# USB-C_BREAKOUT_COMPONENTS.net
KiCad netlist of a schematic drawn in Altium Designer
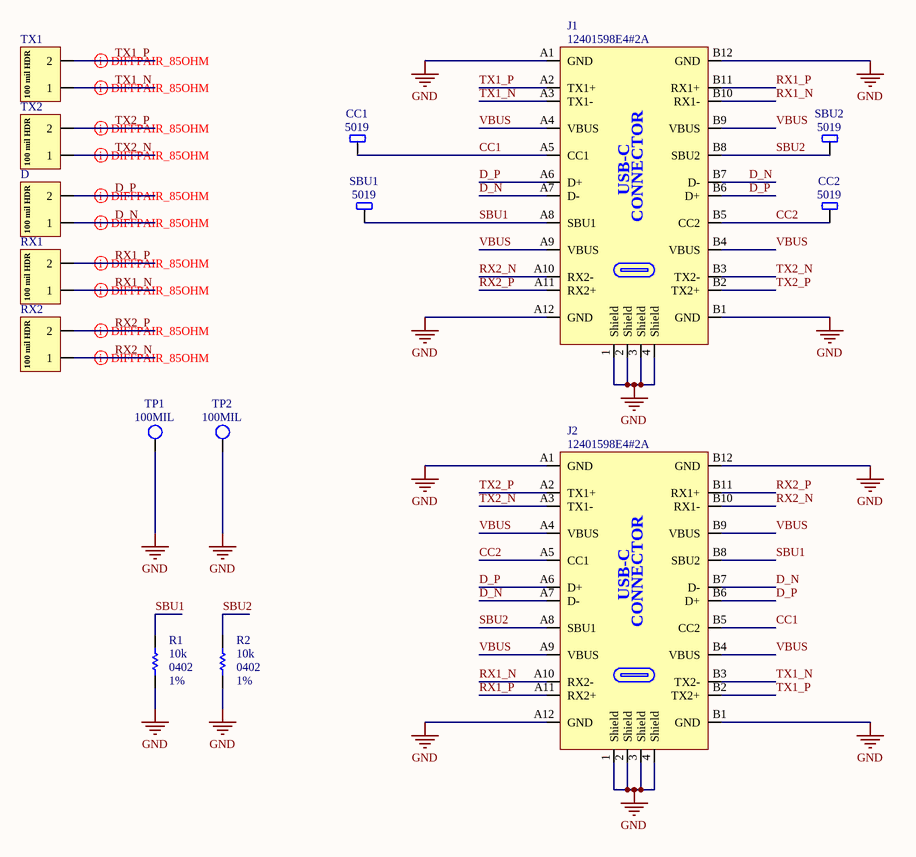
[diagram p0: USB-C_BREAKOUT_COMPONENTS.SchDoc]

(export (version "E")
  (design (tool "Eeschema 10.0.6"))
  (components
    (comp (ref "CC1")
      (value "5019")
      (footprint "GRAMS_MASTER_LIB_PCB:TPO_SMD_5019")
      (description "TPO - PC TEST POINT MINI - SMD")
      (fields
        (field (name "CREATEDBY/DATE") "Olivier Bernard / 5/12/2017")
        (field (name "VERIFIEDBY") "Caroline Paulin / 5 juillet 2018")
      )
      (libsource (lib "GRAMS_MASTER_LIB_SCH") (part "TPO_SMD_5019"))
    )
    (comp (ref "CC2")
      (value "5019")
      (footprint "GRAMS_MASTER_LIB_PCB:TPO_SMD_5019")
      (description "TPO - PC TEST POINT MINI - SMD")
      (fields
        (field (name "CREATEDBY/DATE") "Olivier Bernard / 5/12/2017")
        (field (name "VERIFIEDBY") "Caroline Paulin / 5 juillet 2018")
      )
      (libsource (lib "GRAMS_MASTER_LIB_SCH") (part "TPO_SMD_5019"))
    )
    (comp (ref "D")
      (value "TS-102-G-A")
      (footprint "GRAMS_MASTER_LIB_PCB:CON_HDR_TS-102-G-A")
      (description "CON - HDR 2 position 0.100\" - TH")
      (fields
        (field (name "CREATEDBY/DATE") "Joel Lemay 2018-06-19")
        (field (name "VERIFIEDBY") "Caroline Paulin - 10 sept 2018")
      )
      (libsource (lib "GRAMS_MASTER_LIB_SCH") (part "CON_HDR_TS-102-G-A"))
    )
    (comp (ref "J1")
      (value "12401598E4#2A")
      (footprint "CON_USB_3.2_TypeC_12401598E4#2A")
      (description "CON_USB - USB 3.2 Gen 2 (USB 3.1 Gen 2, Superspeed + (USB 3.1)) 24 pos Receptacle - R/A")
      (fields
        (field (name "CREATEDBY/DATE") "Louis-Daniel Gaulin / 07-04-2021")
        (field (name "VERIFIEDBY") "Philippe Arsenault/2021-04-08")
      )
      (libsource (lib "SWARMUS_LIB") (part "CON_USB_3.2_TypeC_12401598E4#2A"))
    )
    (comp (ref "J2")
      (value "12401598E4#2A")
      (footprint "CON_USB_3.2_TypeC_12401598E4#2A")
      (description "CON_USB - USB 3.2 Gen 2 (USB 3.1 Gen 2, Superspeed + (USB 3.1)) 24 pos Receptacle - R/A")
      (fields
        (field (name "CREATEDBY/DATE") "Louis-Daniel Gaulin / 07-04-2021")
        (field (name "VERIFIEDBY") "Philippe Arsenault/2021-04-08")
      )
      (libsource (lib "SWARMUS_LIB") (part "CON_USB_3.2_TypeC_12401598E4#2A"))
    )
    (comp (ref "R1")
      (value "10k")
      (footprint "GRAMS_MASTER_LIB_PCB:RES_0402")
      (description "RES - 10K OHMS 1% 1/16W - 0402")
      (fields
        (field (name "TOLERANCE") "1%")
        (field (name "PACKAGE") "0402")
        (field (name "Comment") "RC0402FR-0710KL")
        (field (name "CREATEDBY/DATE") "Nicolas V. (2018-11-20)")
        (field (name "VERIFIEDBY") "Nicolas V. (2018-11-20)")
      )
      (libsource (lib "GRAMS_MASTER_LIB_SCH") (part "RES_RC0402FR-0710KL"))
    )
    (comp (ref "R2")
      (value "10k")
      (footprint "GRAMS_MASTER_LIB_PCB:RES_0402")
      (description "RES - 10K OHMS 1% 1/16W - 0402")
      (fields
        (field (name "TOLERANCE") "1%")
        (field (name "PACKAGE") "0402")
        (field (name "Comment") "RC0402FR-0710KL")
        (field (name "CREATEDBY/DATE") "Nicolas V. (2018-11-20)")
        (field (name "VERIFIEDBY") "Nicolas V. (2018-11-20)")
      )
      (libsource (lib "GRAMS_MASTER_LIB_SCH") (part "RES_RC0402FR-0710KL"))
    )
    (comp (ref "RX1")
      (value "TS-102-G-A")
      (footprint "GRAMS_MASTER_LIB_PCB:CON_HDR_TS-102-G-A")
      (description "CON - HDR 2 position 0.100\" - TH")
      (fields
        (field (name "CREATEDBY/DATE") "Joel Lemay 2018-06-19")
        (field (name "VERIFIEDBY") "Caroline Paulin - 10 sept 2018")
      )
      (libsource (lib "GRAMS_MASTER_LIB_SCH") (part "CON_HDR_TS-102-G-A"))
    )
    (comp (ref "RX2")
      (value "TS-102-G-A")
      (footprint "GRAMS_MASTER_LIB_PCB:CON_HDR_TS-102-G-A")
      (description "CON - HDR 2 position 0.100\" - TH")
      (fields
        (field (name "CREATEDBY/DATE") "Joel Lemay 2018-06-19")
        (field (name "VERIFIEDBY") "Caroline Paulin - 10 sept 2018")
      )
      (libsource (lib "GRAMS_MASTER_LIB_SCH") (part "CON_HDR_TS-102-G-A"))
    )
    (comp (ref "SBU1")
      (value "5019")
      (footprint "GRAMS_MASTER_LIB_PCB:TPO_SMD_5019")
      (description "TPO - PC TEST POINT MINI - SMD")
      (fields
        (field (name "CREATEDBY/DATE") "Olivier Bernard / 5/12/2017")
        (field (name "VERIFIEDBY") "Caroline Paulin / 5 juillet 2018")
      )
      (libsource (lib "GRAMS_MASTER_LIB_SCH") (part "TPO_SMD_5019"))
    )
    (comp (ref "SBU2")
      (value "5019")
      (footprint "GRAMS_MASTER_LIB_PCB:TPO_SMD_5019")
      (description "TPO - PC TEST POINT MINI - SMD")
      (fields
        (field (name "CREATEDBY/DATE") "Olivier Bernard / 5/12/2017")
        (field (name "VERIFIEDBY") "Caroline Paulin / 5 juillet 2018")
      )
      (libsource (lib "GRAMS_MASTER_LIB_SCH") (part "TPO_SMD_5019"))
    )
    (comp (ref "TP1")
      (value "100MIL")
      (footprint "grams_master_lib_pcb:TPO_TH_ROUND_100MIL")
      (description "TPO - TEST POINT ROUND TH  - 100MIL")
      (fields
        (field (name "CREATEDBY/DATE") "Louis-Daniel Gaulin/ 14/01/2020")
        (field (name "VERIFIEDBY") "C.Paulin - 21/01/2020")
      )
      (libsource (lib "GRAMS_MASTER_LIB_SCH") (part "TPO_TH_ROUND_100MIL"))
    )
    (comp (ref "TP2")
      (value "100MIL")
      (footprint "grams_master_lib_pcb:TPO_TH_ROUND_100MIL")
      (description "TPO - TEST POINT ROUND TH  - 100MIL")
      (fields
        (field (name "CREATEDBY/DATE") "Louis-Daniel Gaulin/ 14/01/2020")
        (field (name "VERIFIEDBY") "C.Paulin - 21/01/2020")
      )
      (libsource (lib "GRAMS_MASTER_LIB_SCH") (part "TPO_TH_ROUND_100MIL"))
    )
    (comp (ref "TX1")
      (value "TS-102-G-A")
      (footprint "GRAMS_MASTER_LIB_PCB:CON_HDR_TS-102-G-A")
      (description "CON - HDR 2 position 0.100\" - TH")
      (fields
        (field (name "CREATEDBY/DATE") "Joel Lemay 2018-06-19")
        (field (name "VERIFIEDBY") "Caroline Paulin - 10 sept 2018")
      )
      (libsource (lib "GRAMS_MASTER_LIB_SCH") (part "CON_HDR_TS-102-G-A"))
    )
    (comp (ref "TX2")
      (value "TS-102-G-A")
      (footprint "GRAMS_MASTER_LIB_PCB:CON_HDR_TS-102-G-A")
      (description "CON - HDR 2 position 0.100\" - TH")
      (fields
        (field (name "CREATEDBY/DATE") "Joel Lemay 2018-06-19")
        (field (name "VERIFIEDBY") "Caroline Paulin - 10 sept 2018")
      )
      (libsource (lib "GRAMS_MASTER_LIB_SCH") (part "CON_HDR_TS-102-G-A"))
    )
  )
  (nets
    (net (code "1") (name "/CC1") (class "Default")
      (node (ref "CC1") (pin "1") (pinfunction "1_1") (pintype "passive"))
      (node (ref "J1") (pin "A5") (pinfunction "CC1_A5") (pintype "passive"))
      (node (ref "J2") (pin "B5") (pinfunction "CC2_B5") (pintype "passive"))
    )
    (net (code "2") (name "/CC2") (class "Default")
      (node (ref "CC2") (pin "1") (pinfunction "1_1") (pintype "passive"))
      (node (ref "J1") (pin "B5") (pinfunction "CC2_B5") (pintype "passive"))
      (node (ref "J2") (pin "A5") (pinfunction "CC1_A5") (pintype "passive"))
    )
    (net (code "3") (name "/D_N") (class "Default")
      (node (ref "D") (pin "1") (pinfunction "1_1") (pintype "passive"))
      (node (ref "J1") (pin "A7") (pinfunction "D-_A7") (pintype "passive"))
      (node (ref "J1") (pin "B7") (pinfunction "D-_B7") (pintype "passive"))
      (node (ref "J2") (pin "A7") (pinfunction "D-_A7") (pintype "passive"))
      (node (ref "J2") (pin "B7") (pinfunction "D-_B7") (pintype "passive"))
    )
    (net (code "4") (name "/D_P") (class "Default")
      (node (ref "D") (pin "2") (pinfunction "2_2") (pintype "passive"))
      (node (ref "J1") (pin "A6") (pinfunction "D+_A6") (pintype "passive"))
      (node (ref "J1") (pin "B6") (pinfunction "D+_B6") (pintype "passive"))
      (node (ref "J2") (pin "A6") (pinfunction "D+_A6") (pintype "passive"))
      (node (ref "J2") (pin "B6") (pinfunction "D+_B6") (pintype "passive"))
    )
    (net (code "5") (name "/RX1_N") (class "Default")
      (node (ref "J1") (pin "B10") (pinfunction "RX1-_B10") (pintype "passive"))
      (node (ref "J2") (pin "A10") (pinfunction "RX2-_A10") (pintype "passive"))
      (node (ref "RX1") (pin "1") (pinfunction "1_1") (pintype "passive"))
    )
    (net (code "6") (name "/RX1_P") (class "Default")
      (node (ref "J1") (pin "B11") (pinfunction "RX1+_B11") (pintype "passive"))
      (node (ref "J2") (pin "A11") (pinfunction "RX2+_A11") (pintype "passive"))
      (node (ref "RX1") (pin "2") (pinfunction "2_2") (pintype "passive"))
    )
    (net (code "7") (name "/RX2_N") (class "Default")
      (node (ref "J1") (pin "A10") (pinfunction "RX2-_A10") (pintype "passive"))
      (node (ref "J2") (pin "B10") (pinfunction "RX1-_B10") (pintype "passive"))
      (node (ref "RX2") (pin "1") (pinfunction "1_1") (pintype "passive"))
    )
    (net (code "8") (name "/RX2_P") (class "Default")
      (node (ref "J1") (pin "A11") (pinfunction "RX2+_A11") (pintype "passive"))
      (node (ref "J2") (pin "B11") (pinfunction "RX1+_B11") (pintype "passive"))
      (node (ref "RX2") (pin "2") (pinfunction "2_2") (pintype "passive"))
    )
    (net (code "9") (name "/SBU1") (class "Default")
      (node (ref "J1") (pin "A8") (pinfunction "SBU1_A8") (pintype "passive"))
      (node (ref "J2") (pin "B8") (pinfunction "SBU2_B8") (pintype "passive"))
      (node (ref "R1") (pin "1") (pinfunction "1_1") (pintype "passive"))
      (node (ref "SBU1") (pin "1") (pinfunction "1_1") (pintype "passive"))
    )
    (net (code "10") (name "/SBU2") (class "Default")
      (node (ref "J1") (pin "B8") (pinfunction "SBU2_B8") (pintype "passive"))
      (node (ref "J2") (pin "A8") (pinfunction "SBU1_A8") (pintype "passive"))
      (node (ref "R2") (pin "1") (pinfunction "1_1") (pintype "passive"))
      (node (ref "SBU2") (pin "1") (pinfunction "1_1") (pintype "passive"))
    )
    (net (code "11") (name "/TX1_N") (class "Default")
      (node (ref "J1") (pin "A3") (pinfunction "TX1-_A3") (pintype "passive"))
      (node (ref "J2") (pin "B3") (pinfunction "TX2-_B3") (pintype "passive"))
      (node (ref "TX1") (pin "1") (pinfunction "1_1") (pintype "passive"))
    )
    (net (code "12") (name "/TX1_P") (class "Default")
      (node (ref "J1") (pin "A2") (pinfunction "TX1+_A2") (pintype "passive"))
      (node (ref "J2") (pin "B2") (pinfunction "TX2+_B2") (pintype "passive"))
      (node (ref "TX1") (pin "2") (pinfunction "2_2") (pintype "passive"))
    )
    (net (code "13") (name "/TX2_N") (class "Default")
      (node (ref "J1") (pin "B3") (pinfunction "TX2-_B3") (pintype "passive"))
      (node (ref "J2") (pin "A3") (pinfunction "TX1-_A3") (pintype "passive"))
      (node (ref "TX2") (pin "1") (pinfunction "1_1") (pintype "passive"))
    )
    (net (code "14") (name "/TX2_P") (class "Default")
      (node (ref "J1") (pin "B2") (pinfunction "TX2+_B2") (pintype "passive"))
      (node (ref "J2") (pin "A2") (pinfunction "TX1+_A2") (pintype "passive"))
      (node (ref "TX2") (pin "2") (pinfunction "2_2") (pintype "passive"))
    )
    (net (code "15") (name "/VBUS") (class "Default")
      (node (ref "J1") (pin "A4") (pinfunction "VBUS_A4") (pintype "passive"))
      (node (ref "J1") (pin "A9") (pinfunction "VBUS_A9") (pintype "passive"))
      (node (ref "J1") (pin "B4") (pinfunction "VBUS_B4") (pintype "passive"))
      (node (ref "J1") (pin "B9") (pinfunction "VBUS_B9") (pintype "passive"))
      (node (ref "J2") (pin "A4") (pinfunction "VBUS_A4") (pintype "passive"))
      (node (ref "J2") (pin "A9") (pinfunction "VBUS_A9") (pintype "passive"))
      (node (ref "J2") (pin "B4") (pinfunction "VBUS_B4") (pintype "passive"))
      (node (ref "J2") (pin "B9") (pinfunction "VBUS_B9") (pintype "passive"))
    )
    (net (code "16") (name "GND") (class "Default")
      (node (ref "J1") (pin "1") (pinfunction "Shield_1") (pintype "passive"))
      (node (ref "J1") (pin "2") (pinfunction "Shield_2") (pintype "passive"))
      (node (ref "J1") (pin "3") (pinfunction "Shield_3") (pintype "passive"))
      (node (ref "J1") (pin "4") (pinfunction "Shield_4") (pintype "passive"))
      (node (ref "J1") (pin "A1") (pinfunction "GND_A1") (pintype "passive"))
      (node (ref "J1") (pin "A12") (pinfunction "GND_A12") (pintype "passive"))
      (node (ref "J1") (pin "B1") (pinfunction "GND_B1") (pintype "passive"))
      (node (ref "J1") (pin "B12") (pinfunction "GND_B12") (pintype "passive"))
      (node (ref "J2") (pin "1") (pinfunction "Shield_1") (pintype "passive"))
      (node (ref "J2") (pin "2") (pinfunction "Shield_2") (pintype "passive"))
      (node (ref "J2") (pin "3") (pinfunction "Shield_3") (pintype "passive"))
      (node (ref "J2") (pin "4") (pinfunction "Shield_4") (pintype "passive"))
      (node (ref "J2") (pin "A1") (pinfunction "GND_A1") (pintype "passive"))
      (node (ref "J2") (pin "A12") (pinfunction "GND_A12") (pintype "passive"))
      (node (ref "J2") (pin "B1") (pinfunction "GND_B1") (pintype "passive"))
      (node (ref "J2") (pin "B12") (pinfunction "GND_B12") (pintype "passive"))
      (node (ref "R1") (pin "2") (pinfunction "2_2") (pintype "passive"))
      (node (ref "R2") (pin "2") (pinfunction "2_2") (pintype "passive"))
      (node (ref "TP1") (pin "1") (pinfunction "1_1") (pintype "passive"))
      (node (ref "TP2") (pin "1") (pinfunction "1_1") (pintype "passive"))
    )
  )
)
